# DRV8901E.net
KiCad netlist of a schematic drawn in Altium Designer
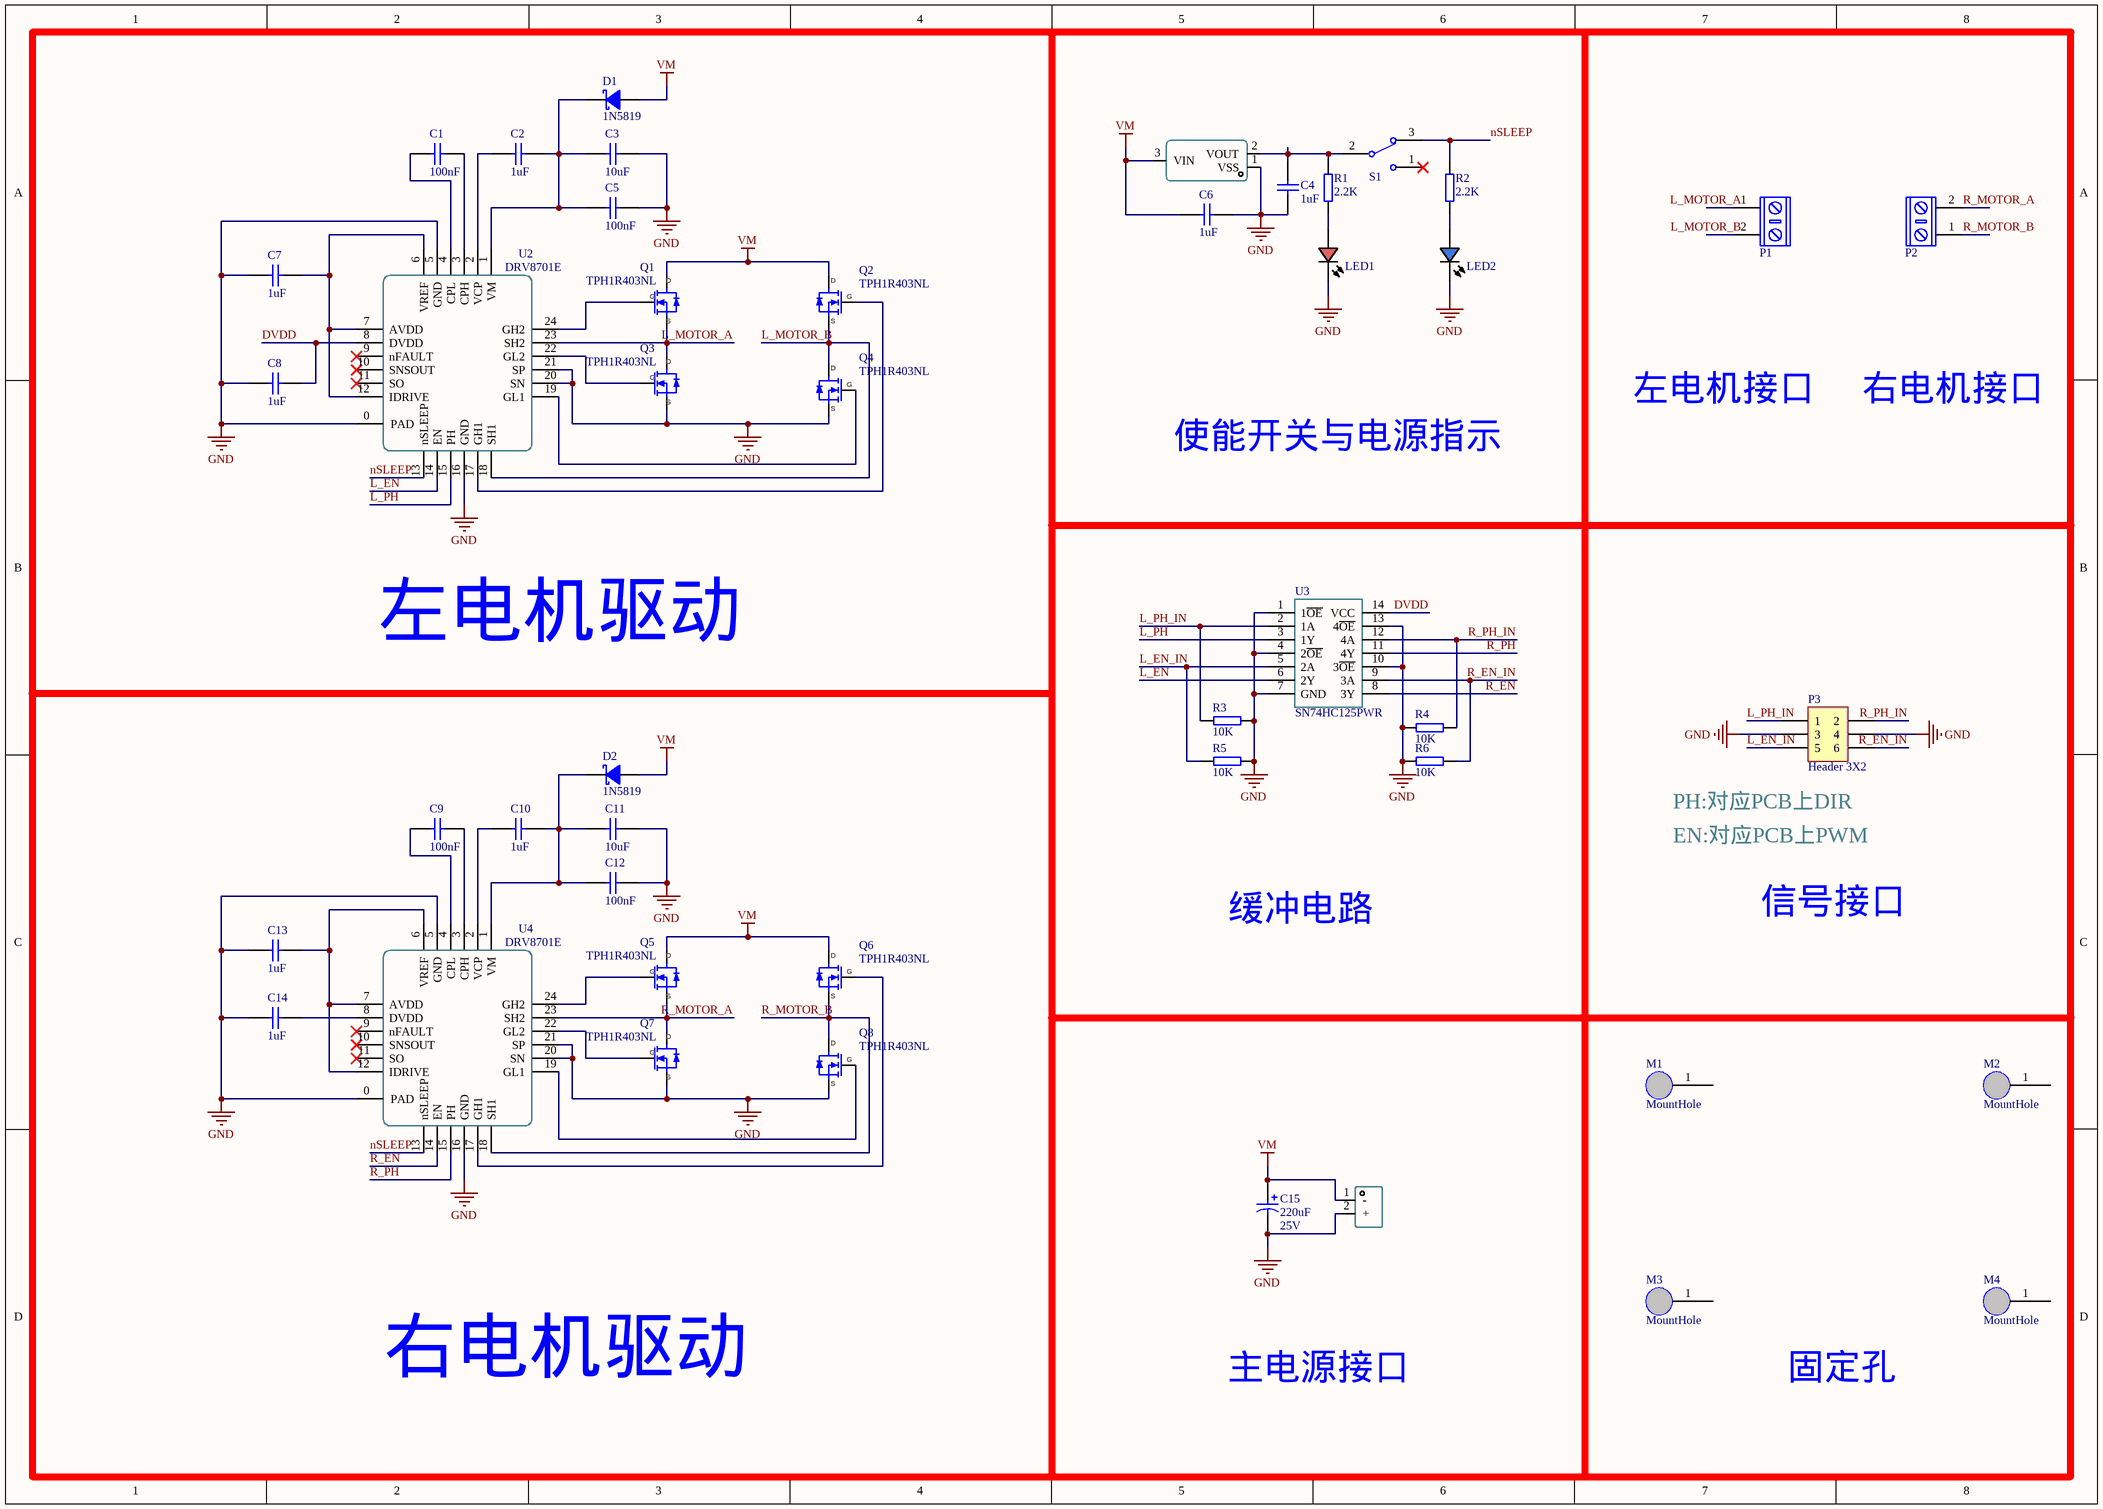
[diagram p0: DRV8901E.SchDoc]

(export (version "E")
  (design (tool "Eeschema 10.0.6"))
  (components
    (comp (ref "C1")
      (value "100nF")
      (footprint "CAPC2012[0805]S-N")
      (description "贴片电容")
      (fields
        (field (name "VOLTAGE") "50V")
        (field (name "TOLERANCE") "±10%")
        (field (name "PUBLISHER") "Altium Limited")
      )
      (libsource (lib "DRV8701_DualMotorDriver") (part "Cap-Chip_1"))
    )
    (comp (ref "C2")
      (value "1uF")
      (footprint "CAPC2012[0805]S-N")
      (description "贴片电容")
      (fields
        (field (name "VOLTAGE") "25V")
        (field (name "TOLERANCE") "±10%")
        (field (name "PUBLISHER") "Altium Limited")
      )
      (libsource (lib "DRV8701_DualMotorDriver") (part "Cap-Chip_2"))
    )
    (comp (ref "C3")
      (value "10uF")
      (footprint "CAPC2012[0805]S-N")
      (description "贴片电容")
      (fields
        (field (name "VOLTAGE") "25V")
        (field (name "TOLERANCE") "±10%")
        (field (name "PUBLISHER") "Altium Limited")
      )
      (libsource (lib "DRV8701_DualMotorDriver") (part "Cap-Chip"))
    )
    (comp (ref "C4")
      (value "1uF")
      (footprint "CAPC2012[0805]S-N")
      (description "贴片电容")
      (fields
        (field (name "VOLTAGE") "25V")
        (field (name "TOLERANCE") "±10%")
        (field (name "PUBLISHER") "Altium Limited")
      )
      (libsource (lib "DRV8701_DualMotorDriver") (part "Cap-Chip_2"))
    )
    (comp (ref "C5")
      (value "100nF")
      (footprint "CAPC2012[0805]S-N")
      (description "贴片电容")
      (fields
        (field (name "VOLTAGE") "50V")
        (field (name "TOLERANCE") "±10%")
        (field (name "PUBLISHER") "Altium Limited")
      )
      (libsource (lib "DRV8701_DualMotorDriver") (part "Cap-Chip_1"))
    )
    (comp (ref "C6")
      (value "1uF")
      (footprint "CAPC2012[0805]S-N")
      (description "贴片电容")
      (fields
        (field (name "VOLTAGE") "25V")
        (field (name "TOLERANCE") "±10%")
        (field (name "PUBLISHER") "Altium Limited")
      )
      (libsource (lib "DRV8701_DualMotorDriver") (part "Cap-Chip_2"))
    )
    (comp (ref "C7")
      (value "1uF")
      (footprint "CAPC2012[0805]S-N")
      (description "贴片电容")
      (fields
        (field (name "VOLTAGE") "25V")
        (field (name "TOLERANCE") "±10%")
        (field (name "PUBLISHER") "Altium Limited")
      )
      (libsource (lib "DRV8701_DualMotorDriver") (part "Cap-Chip_2"))
    )
    (comp (ref "C8")
      (value "1uF")
      (footprint "CAPC2012[0805]S-N")
      (description "贴片电容")
      (fields
        (field (name "VOLTAGE") "25V")
        (field (name "TOLERANCE") "±10%")
        (field (name "PUBLISHER") "Altium Limited")
      )
      (libsource (lib "DRV8701_DualMotorDriver") (part "Cap-Chip_2"))
    )
    (comp (ref "C9")
      (value "100nF")
      (footprint "CAPC2012[0805]S-N")
      (description "贴片电容")
      (fields
        (field (name "VOLTAGE") "50V")
        (field (name "TOLERANCE") "±10%")
        (field (name "PUBLISHER") "Altium Limited")
      )
      (libsource (lib "DRV8701_DualMotorDriver") (part "Cap-Chip_1"))
    )
    (comp (ref "C10")
      (value "1uF")
      (footprint "CAPC2012[0805]S-N")
      (description "贴片电容")
      (fields
        (field (name "VOLTAGE") "25V")
        (field (name "TOLERANCE") "±10%")
        (field (name "PUBLISHER") "Altium Limited")
      )
      (libsource (lib "DRV8701_DualMotorDriver") (part "Cap-Chip_2"))
    )
    (comp (ref "C11")
      (value "10uF")
      (footprint "CAPC2012[0805]S-N")
      (description "贴片电容")
      (fields
        (field (name "VOLTAGE") "25V")
        (field (name "TOLERANCE") "±10%")
        (field (name "PUBLISHER") "Altium Limited")
      )
      (libsource (lib "DRV8701_DualMotorDriver") (part "Cap-Chip"))
    )
    (comp (ref "C12")
      (value "100nF")
      (footprint "CAPC2012[0805]S-N")
      (description "贴片电容")
      (fields
        (field (name "VOLTAGE") "50V")
        (field (name "TOLERANCE") "±10%")
        (field (name "PUBLISHER") "Altium Limited")
      )
      (libsource (lib "DRV8701_DualMotorDriver") (part "Cap-Chip_1"))
    )
    (comp (ref "C13")
      (value "1uF")
      (footprint "CAPC2012[0805]S-N")
      (description "贴片电容")
      (fields
        (field (name "VOLTAGE") "25V")
        (field (name "TOLERANCE") "±10%")
        (field (name "PUBLISHER") "Altium Limited")
      )
      (libsource (lib "DRV8701_DualMotorDriver") (part "Cap-Chip_2"))
    )
    (comp (ref "C14")
      (value "1uF")
      (footprint "CAPC2012[0805]S-N")
      (description "贴片电容")
      (fields
        (field (name "VOLTAGE") "25V")
        (field (name "TOLERANCE") "±10%")
        (field (name "PUBLISHER") "Altium Limited")
      )
      (libsource (lib "DRV8701_DualMotorDriver") (part "Cap-Chip_2"))
    )
    (comp (ref "C15")
      (value "220uF")
      (footprint "CAP-E-S 6.3")
      (description "Polarized Capacitor (Radial)")
      (fields
        (field (name "VOLTAGE") "25V")
        (field (name "Comment") "220uF 25V")
        (field (name "PUBLISHER") "Altium Limited")
      )
      (libsource (lib "DRV8701_DualMotorDriver") (part "Cap-Elect"))
    )
    (comp (ref "D1")
      (value "1N5819")
      (footprint "SOD-123-L")
      (description "肖特基二极管 Diode")
      (fields (field (name "PARTNUMBER") "1N5819") (field (name "PUBLISHER") "Altium Limited"))
      (libsource (lib "DRV8701_DualMotorDriver") (part "Diode Schottky"))
    )
    (comp (ref "D2")
      (value "1N5819")
      (footprint "SOD-123-L")
      (description "肖特基二极管 Diode")
      (fields (field (name "PARTNUMBER") "1N5819") (field (name "PUBLISHER") "Altium Limited"))
      (libsource (lib "DRV8701_DualMotorDriver") (part "Diode Schottky"))
    )
    (comp (ref "LED1")
      (value "~")
      (footprint "LED_0805")
      (description "Typical Chip LED")
      (fields (field (name "PUBLISHER") "Altium Limited"))
      (libsource (lib "DRV8701_DualMotorDriver") (part "LED Chip Red"))
    )
    (comp (ref "LED2")
      (value "Blue")
      (footprint "LED_0805")
      (description "Typical Chip LED")
      (fields (field (name "PUBLISHER") "Altium Limited"))
      (libsource (lib "DRV8701_DualMotorDriver") (part "LED Chip Blue"))
    )
    (comp (ref "M1")
      (value "MountHole")
      (footprint "M3-MountSlot")
      (description "固定孔")
      (libsource (lib "DRV8701_DualMotorDriver") (part "MountHole"))
    )
    (comp (ref "M2")
      (value "MountHole")
      (footprint "M3-MountSlot")
      (description "固定孔")
      (libsource (lib "DRV8701_DualMotorDriver") (part "MountHole"))
    )
    (comp (ref "M3")
      (value "MountHole")
      (footprint "M3-MountSlot")
      (description "固定孔")
      (libsource (lib "DRV8701_DualMotorDriver") (part "MountHole"))
    )
    (comp (ref "M4")
      (value "MountHole")
      (footprint "M3-MountSlot")
      (description "固定孔")
      (libsource (lib "DRV8701_DualMotorDriver") (part "MountHole"))
    )
    (comp (ref "P1")
      (value "KF/WJ/DG 30x connecter")
      (footprint "KF/WJ/DG 301-2p-5.0mm")
      (description "接线端子 2Pin")
      (libsource (lib "DRV8701_DualMotorDriver") (part "KF/WJ/DG 30x"))
    )
    (comp (ref "P2")
      (value "KF/WJ/DG 30x connecter")
      (footprint "KF/WJ/DG 301-2p-5.0mm")
      (description "接线端子 2Pin")
      (libsource (lib "DRV8701_DualMotorDriver") (part "KF/WJ/DG 30x"))
    )
    (comp (ref "P3")
      (value "Header 3X2")
      (footprint "HDR2X3")
      (description "Header, 3-Pin, Dual row")
      (fields (field (name "PUBLISHER") "Altium Limited"))
      (libsource (lib "DRV8701_DualMotorDriver") (part "Header 3X2"))
    )
    (comp (ref "Q1")
      (value "TPH1R403NL")
      (footprint "DFN5x6")
      (description "东芝 N沟 MOS")
      (libsource (lib "DRV8701_DualMotorDriver") (part "TPH1R403NL"))
    )
    (comp (ref "Q2")
      (value "TPH1R403NL")
      (footprint "DFN5x6")
      (description "东芝 N沟 MOS")
      (libsource (lib "DRV8701_DualMotorDriver") (part "TPH1R403NL"))
    )
    (comp (ref "Q3")
      (value "TPH1R403NL")
      (footprint "DFN5x6")
      (description "东芝 N沟 MOS")
      (libsource (lib "DRV8701_DualMotorDriver") (part "TPH1R403NL"))
    )
    (comp (ref "Q4")
      (value "TPH1R403NL")
      (footprint "DFN5x6")
      (description "东芝 N沟 MOS")
      (libsource (lib "DRV8701_DualMotorDriver") (part "TPH1R403NL"))
    )
    (comp (ref "Q5")
      (value "TPH1R403NL")
      (footprint "DFN5x6")
      (description "东芝 N沟 MOS")
      (libsource (lib "DRV8701_DualMotorDriver") (part "TPH1R403NL"))
    )
    (comp (ref "Q6")
      (value "TPH1R403NL")
      (footprint "DFN5x6")
      (description "东芝 N沟 MOS")
      (libsource (lib "DRV8701_DualMotorDriver") (part "TPH1R403NL"))
    )
    (comp (ref "Q7")
      (value "TPH1R403NL")
      (footprint "DFN5x6")
      (description "东芝 N沟 MOS")
      (libsource (lib "DRV8701_DualMotorDriver") (part "TPH1R403NL"))
    )
    (comp (ref "Q8")
      (value "TPH1R403NL")
      (footprint "DFN5x6")
      (description "东芝 N沟 MOS")
      (libsource (lib "DRV8701_DualMotorDriver") (part "TPH1R403NL"))
    )
    (comp (ref "R1")
      (value "2.2K")
      (footprint "R0805")
      (description "贴片电阻")
      (fields
        (field (name "TOLERANCE") "±1%")
        (field (name "Comment") "2.2K ±1%")
        (field (name "PUBLISHER") "Altium Limited")
      )
      (libsource (lib "DRV8701_DualMotorDriver") (part "Res-Chip"))
    )
    (comp (ref "R2")
      (value "2.2K")
      (footprint "R0805")
      (description "贴片电阻")
      (fields
        (field (name "TOLERANCE") "±1%")
        (field (name "Comment") "2.2K ±1%")
        (field (name "PUBLISHER") "Altium Limited")
      )
      (libsource (lib "DRV8701_DualMotorDriver") (part "Res-Chip"))
    )
    (comp (ref "R3")
      (value "10K")
      (footprint "R0805")
      (description "贴片电阻")
      (fields
        (field (name "TOLERANCE") "±1%")
        (field (name "Comment") "10K ±1%")
        (field (name "PUBLISHER") "Altium Limited")
      )
      (libsource (lib "DRV8701_DualMotorDriver") (part "Res-Chip_1"))
    )
    (comp (ref "R4")
      (value "10K")
      (footprint "R0805")
      (description "贴片电阻")
      (fields
        (field (name "TOLERANCE") "±1%")
        (field (name "Comment") "10K ±1%")
        (field (name "PUBLISHER") "Altium Limited")
      )
      (libsource (lib "DRV8701_DualMotorDriver") (part "Res-Chip_1"))
    )
    (comp (ref "R5")
      (value "10K")
      (footprint "R0805")
      (description "贴片电阻")
      (fields
        (field (name "TOLERANCE") "±1%")
        (field (name "Comment") "10K ±1%")
        (field (name "PUBLISHER") "Altium Limited")
      )
      (libsource (lib "DRV8701_DualMotorDriver") (part "Res-Chip_1"))
    )
    (comp (ref "R6")
      (value "10K")
      (footprint "R0805")
      (description "贴片电阻")
      (fields
        (field (name "TOLERANCE") "±1%")
        (field (name "Comment") "10K ±1%")
        (field (name "PUBLISHER") "Altium Limited")
      )
      (libsource (lib "DRV8701_DualMotorDriver") (part "Res-Chip_1"))
    )
    (comp (ref "S1")
      (value "SW-SPDT")
      (footprint "SS12D10")
      (description "单刀双掷开关 3脚船型、钮子、拨动开关 SPDT Subminiature Toggle Switch")
      (fields (field (name "PUBLISHER") "Altium Limited"))
      (libsource (lib "DRV8701_DualMotorDriver") (part "SW-SPDT"))
    )
    (comp (ref "U1")
      (value "LR8341A-T33")
      (footprint "SOT-23-3L_L2.9-W1.6-P1.90-LS2.8-BL")
      (fields (field (name "MANUFACTURER") "LR(朗瑞)"))
      (libsource (lib "DRV8701_DualMotorDriver") (part "LR8341A-T33"))
    )
    (comp (ref "U2")
      (value "DRV8701E")
      (footprint "QFN24-4x4")
      (description "DRV8701E Ti全桥驱动芯片")
      (libsource (lib "DRV8701_DualMotorDriver") (part "DRV8701E"))
    )
    (comp (ref "U3")
      (value "SN74HC125PWR")
      (footprint "TSSOP-14")
      (description "三态输出的四路缓冲器 TSSOP-20")
      (libsource (lib "DRV8701_DualMotorDriver") (part "SN74HC125PWR"))
    )
    (comp (ref "U4")
      (value "DRV8701E")
      (footprint "QFN24-4x4")
      (description "DRV8701E Ti全桥驱动芯片")
      (libsource (lib "DRV8701_DualMotorDriver") (part "DRV8701E"))
    )
    (comp (ref "U5")
      (value "XT60")
      (footprint "CONN-TH_XT60")
      (fields (field (name "MANUFACTURER") "AMASS(艾迈斯)"))
      (libsource (lib "DRV8701_DualMotorDriver") (part "XT60"))
    )
  )
  (nets
    (net (code "1") (name "/DVDD") (class "Default")
      (node (ref "C8") (pin "2") (pinfunction "2_2") (pintype "passive"))
      (node (ref "U2") (pin "8") (pinfunction "DVDD_8") (pintype "passive"))
      (node (ref "U3") (pin "14") (pinfunction "VCC_14") (pintype "passive"))
    )
    (net (code "2") (name "/L_EN") (class "Default")
      (node (ref "U2") (pin "14") (pinfunction "EN_14") (pintype "passive"))
      (node (ref "U3") (pin "6") (pinfunction "2Y_6") (pintype "passive"))
    )
    (net (code "3") (name "/L_EN_IN") (class "Default")
      (node (ref "P3") (pin "5") (pinfunction "5_5") (pintype "passive"))
      (node (ref "R5") (pin "1") (pinfunction "1_1") (pintype "passive"))
      (node (ref "U3") (pin "5") (pinfunction "2A_5") (pintype "passive"))
    )
    (net (code "4") (name "/L_MOTOR_A") (class "Default")
      (node (ref "P1") (pin "1") (pinfunction "1_1") (pintype "passive"))
      (node (ref "Q1") (pin "3") (pinfunction "S_3") (pintype "passive"))
      (node (ref "Q3") (pin "1") (pinfunction "D_1") (pintype "passive"))
      (node (ref "U2") (pin "23") (pinfunction "SH2_23") (pintype "passive"))
    )
    (net (code "5") (name "/L_MOTOR_B") (class "Default")
      (node (ref "P1") (pin "2") (pinfunction "2_2") (pintype "passive"))
      (node (ref "Q2") (pin "3") (pinfunction "S_3") (pintype "passive"))
      (node (ref "Q4") (pin "1") (pinfunction "D_1") (pintype "passive"))
      (node (ref "U2") (pin "18") (pinfunction "SH1_18") (pintype "passive"))
    )
    (net (code "6") (name "/L_PH") (class "Default")
      (node (ref "U2") (pin "15") (pinfunction "PH_15") (pintype "passive"))
      (node (ref "U3") (pin "3") (pinfunction "1Y_3") (pintype "passive"))
    )
    (net (code "7") (name "/L_PH_IN") (class "Default")
      (node (ref "P3") (pin "1") (pinfunction "1_1") (pintype "passive"))
      (node (ref "R3") (pin "1") (pinfunction "1_1") (pintype "passive"))
      (node (ref "U3") (pin "2") (pinfunction "1A_2") (pintype "passive"))
    )
    (net (code "8") (name "/R_EN") (class "Default")
      (node (ref "U3") (pin "8") (pinfunction "3Y_8") (pintype "passive"))
      (node (ref "U4") (pin "14") (pinfunction "EN_14") (pintype "passive"))
    )
    (net (code "9") (name "/R_EN_IN") (class "Default")
      (node (ref "P3") (pin "6") (pinfunction "6_6") (pintype "passive"))
      (node (ref "R6") (pin "1") (pinfunction "1_1") (pintype "passive"))
      (node (ref "U3") (pin "9") (pinfunction "3A_9") (pintype "passive"))
    )
    (net (code "10") (name "/R_MOTOR_A") (class "Default")
      (node (ref "P2") (pin "2") (pinfunction "2_2") (pintype "passive"))
      (node (ref "Q5") (pin "3") (pinfunction "S_3") (pintype "passive"))
      (node (ref "Q7") (pin "1") (pinfunction "D_1") (pintype "passive"))
      (node (ref "U4") (pin "23") (pinfunction "SH2_23") (pintype "passive"))
    )
    (net (code "11") (name "/R_MOTOR_B") (class "Default")
      (node (ref "P2") (pin "1") (pinfunction "1_1") (pintype "passive"))
      (node (ref "Q6") (pin "3") (pinfunction "S_3") (pintype "passive"))
      (node (ref "Q8") (pin "1") (pinfunction "D_1") (pintype "passive"))
      (node (ref "U4") (pin "18") (pinfunction "SH1_18") (pintype "passive"))
    )
    (net (code "12") (name "/R_PH") (class "Default")
      (node (ref "U3") (pin "11") (pinfunction "4Y_11") (pintype "passive"))
      (node (ref "U4") (pin "15") (pinfunction "PH_15") (pintype "passive"))
    )
    (net (code "13") (name "/R_PH_IN") (class "Default")
      (node (ref "P3") (pin "2") (pinfunction "2_2") (pintype "passive"))
      (node (ref "R4") (pin "1") (pinfunction "1_1") (pintype "passive"))
      (node (ref "U3") (pin "12") (pinfunction "4A_12") (pintype "passive"))
    )
    (net (code "14") (name "/nSLEEP") (class "Default")
      (node (ref "R2") (pin "2") (pinfunction "2_2") (pintype "passive"))
      (node (ref "S1") (pin "3") (pintype "passive"))
      (node (ref "U2") (pin "13") (pinfunction "nSLEEP_13") (pintype "passive"))
      (node (ref "U4") (pin "13") (pinfunction "nSLEEP_13") (pintype "passive"))
    )
    (net (code "15") (name "GND") (class "Default")
      (node (ref "C11") (pin "2") (pinfunction "2_2") (pintype "passive"))
      (node (ref "C12") (pin "2") (pinfunction "2_2") (pintype "passive"))
      (node (ref "C13") (pin "1") (pinfunction "1_1") (pintype "passive"))
      (node (ref "C14") (pin "1") (pinfunction "1_1") (pintype "passive"))
      (node (ref "C15") (pin "2") (pinfunction "2_2") (pintype "passive"))
      (node (ref "C3") (pin "2") (pinfunction "2_2") (pintype "passive"))
      (node (ref "C4") (pin "1") (pinfunction "1_1") (pintype "passive"))
      (node (ref "C5") (pin "2") (pinfunction "2_2") (pintype "passive"))
      (node (ref "C6") (pin "1") (pinfunction "1_1") (pintype "passive"))
      (node (ref "C7") (pin "1") (pinfunction "1_1") (pintype "passive"))
      (node (ref "C8") (pin "1") (pinfunction "1_1") (pintype "passive"))
      (node (ref "LED1") (pin "C") (pinfunction "C_C") (pintype "passive"))
      (node (ref "LED2") (pin "C") (pinfunction "C_C") (pintype "passive"))
      (node (ref "P3") (pin "3") (pinfunction "3_3") (pintype "passive"))
      (node (ref "P3") (pin "4") (pinfunction "4_4") (pintype "passive"))
      (node (ref "Q3") (pin "3") (pinfunction "S_3") (pintype "passive"))
      (node (ref "Q4") (pin "3") (pinfunction "S_3") (pintype "passive"))
      (node (ref "Q7") (pin "3") (pinfunction "S_3") (pintype "passive"))
      (node (ref "Q8") (pin "3") (pinfunction "S_3") (pintype "passive"))
      (node (ref "R3") (pin "2") (pinfunction "2_2") (pintype "passive"))
      (node (ref "R4") (pin "2") (pinfunction "2_2") (pintype "passive"))
      (node (ref "R5") (pin "2") (pinfunction "2_2") (pintype "passive"))
      (node (ref "R6") (pin "2") (pinfunction "2_2") (pintype "passive"))
      (node (ref "U1") (pin "1") (pinfunction "VSS_1") (pintype "passive"))
      (node (ref "U2") (pin "0") (pinfunction "PAD_0") (pintype "passive"))
      (node (ref "U2") (pin "16") (pinfunction "GND_16") (pintype "passive"))
      (node (ref "U2") (pin "20") (pinfunction "SN_20") (pintype "passive"))
      (node (ref "U2") (pin "21") (pinfunction "SP_21") (pintype "passive"))
      (node (ref "U2") (pin "5") (pinfunction "GND_5") (pintype "passive"))
      (node (ref "U3") (pin "1") (pinfunction "1~{OE}_1") (pintype "passive"))
      (node (ref "U3") (pin "10") (pinfunction "3~{OE}_10") (pintype "passive"))
      (node (ref "U3") (pin "13") (pinfunction "4~{OE}_13") (pintype "passive"))
      (node (ref "U3") (pin "4") (pinfunction "2~{OE}_4") (pintype "passive"))
      (node (ref "U3") (pin "7") (pinfunction "GND_7") (pintype "passive"))
      (node (ref "U4") (pin "0") (pinfunction "PAD_0") (pintype "passive"))
      (node (ref "U4") (pin "16") (pinfunction "GND_16") (pintype "passive"))
      (node (ref "U4") (pin "20") (pinfunction "SN_20") (pintype "passive"))
      (node (ref "U4") (pin "21") (pinfunction "SP_21") (pintype "passive"))
      (node (ref "U4") (pin "5") (pinfunction "GND_5") (pintype "passive"))
      (node (ref "U5") (pin "2") (pinfunction "+_2") (pintype "passive"))
    )
    (net (code "16") (name "Net-(LED1-PadA)") (class "Default")
      (node (ref "LED1") (pin "A") (pinfunction "A_A") (pintype "passive"))
      (node (ref "R1") (pin "1") (pinfunction "1_1") (pintype "passive"))
    )
    (net (code "17") (name "Net-(LED2-PadA)") (class "Default")
      (node (ref "LED2") (pin "A") (pinfunction "A_A") (pintype "passive"))
      (node (ref "R2") (pin "1") (pinfunction "1_1") (pintype "passive"))
    )
    (net (code "18") (name "Net-(Q1-G)") (class "Default")
      (node (ref "Q1") (pin "2") (pinfunction "G_2") (pintype "passive"))
      (node (ref "U2") (pin "24") (pinfunction "GH2_24") (pintype "passive"))
    )
    (net (code "19") (name "Net-(Q2-G)") (class "Default")
      (node (ref "Q2") (pin "2") (pinfunction "G_2") (pintype "passive"))
      (node (ref "U2") (pin "17") (pinfunction "GH1_17") (pintype "passive"))
    )
    (net (code "20") (name "Net-(Q3-G)") (class "Default")
      (node (ref "Q3") (pin "2") (pinfunction "G_2") (pintype "passive"))
      (node (ref "U2") (pin "22") (pinfunction "GL2_22") (pintype "passive"))
    )
    (net (code "21") (name "Net-(Q4-G)") (class "Default")
      (node (ref "Q4") (pin "2") (pinfunction "G_2") (pintype "passive"))
      (node (ref "U2") (pin "19") (pinfunction "GL1_19") (pintype "passive"))
    )
    (net (code "22") (name "Net-(Q5-G)") (class "Default")
      (node (ref "Q5") (pin "2") (pinfunction "G_2") (pintype "passive"))
      (node (ref "U4") (pin "24") (pinfunction "GH2_24") (pintype "passive"))
    )
    (net (code "23") (name "Net-(Q6-G)") (class "Default")
      (node (ref "Q6") (pin "2") (pinfunction "G_2") (pintype "passive"))
      (node (ref "U4") (pin "17") (pinfunction "GH1_17") (pintype "passive"))
    )
    (net (code "24") (name "Net-(Q7-G)") (class "Default")
      (node (ref "Q7") (pin "2") (pinfunction "G_2") (pintype "passive"))
      (node (ref "U4") (pin "22") (pinfunction "GL2_22") (pintype "passive"))
    )
    (net (code "25") (name "Net-(Q8-G)") (class "Default")
      (node (ref "Q8") (pin "2") (pinfunction "G_2") (pintype "passive"))
      (node (ref "U4") (pin "19") (pinfunction "GL1_19") (pintype "passive"))
    )
    (net (code "26") (name "Net-(U1-VOUT)") (class "Default")
      (node (ref "C4") (pin "2") (pinfunction "2_2") (pintype "passive"))
      (node (ref "R1") (pin "2") (pinfunction "2_2") (pintype "passive"))
      (node (ref "S1") (pin "2") (pintype "passive"))
      (node (ref "U1") (pin "2") (pinfunction "VOUT_2") (pintype "passive"))
    )
    (net (code "27") (name "Net-(U2-AVDD)") (class "Default")
      (node (ref "C7") (pin "2") (pinfunction "2_2") (pintype "passive"))
      (node (ref "U2") (pin "12") (pinfunction "IDRIVE_12") (pintype "passive"))
      (node (ref "U2") (pin "6") (pinfunction "VREF_6") (pintype "passive"))
      (node (ref "U2") (pin "7") (pinfunction "AVDD_7") (pintype "passive"))
    )
    (net (code "28") (name "Net-(U2-CPH)") (class "Default")
      (node (ref "C1") (pin "2") (pinfunction "2_2") (pintype "passive"))
      (node (ref "U2") (pin "3") (pinfunction "CPH_3") (pintype "passive"))
    )
    (net (code "29") (name "Net-(U2-CPL)") (class "Default")
      (node (ref "C1") (pin "1") (pinfunction "1_1") (pintype "passive"))
      (node (ref "U2") (pin "4") (pinfunction "CPL_4") (pintype "passive"))
    )
    (net (code "30") (name "Net-(U2-VCP)") (class "Default")
      (node (ref "C2") (pin "1") (pinfunction "1_1") (pintype "passive"))
      (node (ref "U2") (pin "2") (pinfunction "VCP_2") (pintype "passive"))
    )
    (net (code "31") (name "Net-(U2-VM)") (class "Default")
      (node (ref "C2") (pin "2") (pinfunction "2_2") (pintype "passive"))
      (node (ref "C3") (pin "1") (pinfunction "1_1") (pintype "passive"))
      (node (ref "C5") (pin "1") (pinfunction "1_1") (pintype "passive"))
      (node (ref "D1") (pin "K") (pinfunction "K_K") (pintype "passive"))
      (node (ref "U2") (pin "1") (pinfunction "VM_1") (pintype "passive"))
    )
    (net (code "32") (name "Net-(U4-AVDD)") (class "Default")
      (node (ref "C13") (pin "2") (pinfunction "2_2") (pintype "passive"))
      (node (ref "U4") (pin "12") (pinfunction "IDRIVE_12") (pintype "passive"))
      (node (ref "U4") (pin "6") (pinfunction "VREF_6") (pintype "passive"))
      (node (ref "U4") (pin "7") (pinfunction "AVDD_7") (pintype "passive"))
    )
    (net (code "33") (name "Net-(U4-CPH)") (class "Default")
      (node (ref "C9") (pin "2") (pinfunction "2_2") (pintype "passive"))
      (node (ref "U4") (pin "3") (pinfunction "CPH_3") (pintype "passive"))
    )
    (net (code "34") (name "Net-(U4-CPL)") (class "Default")
      (node (ref "C9") (pin "1") (pinfunction "1_1") (pintype "passive"))
      (node (ref "U4") (pin "4") (pinfunction "CPL_4") (pintype "passive"))
    )
    (net (code "35") (name "Net-(U4-DVDD)") (class "Default")
      (node (ref "C14") (pin "2") (pinfunction "2_2") (pintype "passive"))
      (node (ref "U4") (pin "8") (pinfunction "DVDD_8") (pintype "passive"))
    )
    (net (code "36") (name "Net-(U4-VCP)") (class "Default")
      (node (ref "C10") (pin "1") (pinfunction "1_1") (pintype "passive"))
      (node (ref "U4") (pin "2") (pinfunction "VCP_2") (pintype "passive"))
    )
    (net (code "37") (name "Net-(U4-VM)") (class "Default")
      (node (ref "C10") (pin "2") (pinfunction "2_2") (pintype "passive"))
      (node (ref "C11") (pin "1") (pinfunction "1_1") (pintype "passive"))
      (node (ref "C12") (pin "1") (pinfunction "1_1") (pintype "passive"))
      (node (ref "D2") (pin "K") (pinfunction "K_K") (pintype "passive"))
      (node (ref "U4") (pin "1") (pinfunction "VM_1") (pintype "passive"))
    )
    (net (code "38") (name "VM") (class "Default")
      (node (ref "C15") (pin "1") (pinfunction "1_1") (pintype "passive"))
      (node (ref "C6") (pin "2") (pinfunction "2_2") (pintype "passive"))
      (node (ref "D1") (pin "A") (pinfunction "A_A") (pintype "passive"))
      (node (ref "D2") (pin "A") (pinfunction "A_A") (pintype "passive"))
      (node (ref "Q1") (pin "1") (pinfunction "D_1") (pintype "passive"))
      (node (ref "Q2") (pin "1") (pinfunction "D_1") (pintype "passive"))
      (node (ref "Q5") (pin "1") (pinfunction "D_1") (pintype "passive"))
      (node (ref "Q6") (pin "1") (pinfunction "D_1") (pintype "passive"))
      (node (ref "U1") (pin "3") (pinfunction "VIN_3") (pintype "passive"))
      (node (ref "U5") (pin "1") (pinfunction "-_1") (pintype "passive"))
    )
    (net (code "39") (name "unconnected-(M1-Pad1)") (class "Default")
      (node (ref "M1") (pin "1") (pinfunction "1_1") (pintype "passive"))
    )
    (net (code "40") (name "unconnected-(M2-Pad1)") (class "Default")
      (node (ref "M2") (pin "1") (pinfunction "1_1") (pintype "passive"))
    )
    (net (code "41") (name "unconnected-(M3-Pad1)") (class "Default")
      (node (ref "M3") (pin "1") (pinfunction "1_1") (pintype "passive"))
    )
    (net (code "42") (name "unconnected-(M4-Pad1)") (class "Default")
      (node (ref "M4") (pin "1") (pinfunction "1_1") (pintype "passive"))
    )
    (net (code "43") (name "unconnected-(S1-Pad1)") (class "Default")
      (node (ref "S1") (pin "1") (pintype "passive+no_connect"))
    )
    (net (code "44") (name "unconnected-(U2-SNSOUT-Pad10)") (class "Default")
      (node (ref "U2") (pin "10") (pinfunction "SNSOUT_10") (pintype "passive+no_connect"))
    )
    (net (code "45") (name "unconnected-(U2-SO-Pad11)") (class "Default")
      (node (ref "U2") (pin "11") (pinfunction "SO_11") (pintype "passive+no_connect"))
    )
    (net (code "46") (name "unconnected-(U2-nFAULT-Pad9)") (class "Default")
      (node (ref "U2") (pin "9") (pinfunction "nFAULT_9") (pintype "passive+no_connect"))
    )
    (net (code "47") (name "unconnected-(U4-SNSOUT-Pad10)") (class "Default")
      (node (ref "U4") (pin "10") (pinfunction "SNSOUT_10") (pintype "passive+no_connect"))
    )
    (net (code "48") (name "unconnected-(U4-SO-Pad11)") (class "Default")
      (node (ref "U4") (pin "11") (pinfunction "SO_11") (pintype "passive+no_connect"))
    )
    (net (code "49") (name "unconnected-(U4-nFAULT-Pad9)") (class "Default")
      (node (ref "U4") (pin "9") (pinfunction "nFAULT_9") (pintype "passive+no_connect"))
    )
  )
)
